# devboard.net
KiCad netlist of a schematic drawn in EAGLE
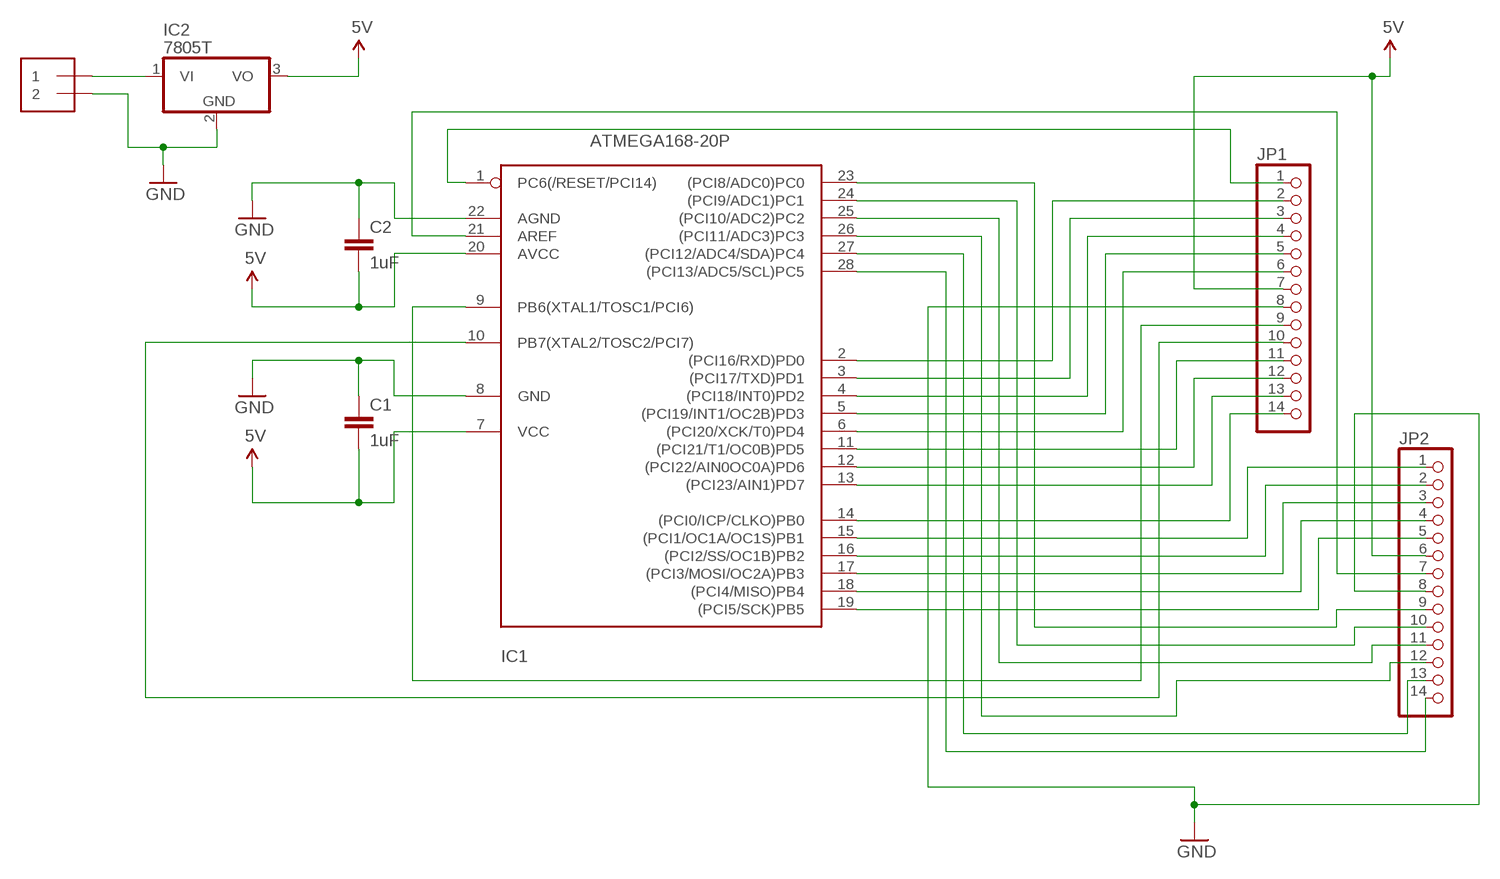
[diagram p0: schematic, sheet 1]

(export (version "E")
  (design (tool "Eeschema 10.0.6"))
  (components
    (comp (ref "C1")
      (value "1uF")
      (footprint "eagle-import:CAP-PTH-SMALL")
      (libsource (lib "eagle-import") (part "CAPPTH"))
    )
    (comp (ref "C2")
      (value "1uF")
      (footprint "eagle-import:CAP-PTH-SMALL")
      (libsource (lib "eagle-import") (part "CAPPTH"))
    )
    (comp (ref "IC1")
      (value "ATMEGA168-20P")
      (footprint "eagle-import:DIL28-3")
      (libsource (lib "eagle-import") (part "ATMEGA168P-20"))
    )
    (comp (ref "IC2")
      (value "7805T")
      (footprint "eagle-import:TO220H")
      (libsource (lib "eagle-import") (part "78T05"))
    )
    (comp (ref "JP1")
      (value "PINHD-1X14")
      (footprint "eagle-import:1X14")
      (libsource (lib "eagle-import") (part "PINHD-1X14"))
    )
    (comp (ref "JP2")
      (value "PINHD-1X14")
      (footprint "eagle-import:1X14")
      (libsource (lib "eagle-import") (part "PINHD-1X14"))
    )
    (comp (ref "POWER_IN")
      (value "1X2-3.5MM")
      (footprint "eagle-import:1X2-3.5MM")
      (libsource (lib "eagle-import") (part "1X2-3.5MM"))
    )
  )
  (nets
    (net (code "1") (name "5V") (class "Default")
      (node (ref "C1") (pin "2") (pinfunction "2_2") (pintype "passive"))
      (node (ref "C2") (pin "2") (pinfunction "2_2") (pintype "passive"))
      (node (ref "IC1") (pin "20") (pinfunction "AVCC_20") (pintype "bidirectional"))
      (node (ref "IC1") (pin "7") (pinfunction "VCC_7") (pintype "bidirectional"))
      (node (ref "IC2") (pin "3") (pinfunction "VO_3") (pintype "passive"))
      (node (ref "JP1") (pin "7") (pinfunction "7_7") (pintype "passive"))
      (node (ref "JP2") (pin "6") (pinfunction "6_6") (pintype "passive"))
    )
    (net (code "2") (name "GND") (class "Default")
      (node (ref "C1") (pin "1") (pinfunction "1_1") (pintype "passive"))
      (node (ref "C2") (pin "1") (pinfunction "1_1") (pintype "passive"))
      (node (ref "IC1") (pin "22") (pinfunction "AGND_22") (pintype "bidirectional"))
      (node (ref "IC1") (pin "8") (pinfunction "GND_8") (pintype "bidirectional"))
      (node (ref "IC2") (pin "2") (pinfunction "GND_2") (pintype "passive"))
      (node (ref "JP1") (pin "8") (pinfunction "8_8") (pintype "passive"))
      (node (ref "JP2") (pin "8") (pinfunction "8_8") (pintype "passive"))
      (node (ref "POWER_IN") (pin "2") (pinfunction "2_2") (pintype "passive"))
    )
    (net (code "3") (name "Net-(IC1-(PCI0{slash}ICP{slash}CLKO)PB0)") (class "Default")
      (node (ref "IC1") (pin "14") (pinfunction "(PCI0/ICP/CLKO)PB0_14") (pintype "bidirectional"))
      (node (ref "JP1") (pin "14") (pinfunction "14_14") (pintype "passive"))
    )
    (net (code "4") (name "Net-(IC1-(PCI1{slash}OC1A{slash}OC1S)PB1)") (class "Default")
      (node (ref "IC1") (pin "15") (pinfunction "(PCI1/OC1A/OC1S)PB1_15") (pintype "bidirectional"))
      (node (ref "JP2") (pin "1") (pinfunction "1_1") (pintype "passive"))
    )
    (net (code "5") (name "Net-(IC1-(PCI2{slash}SS{slash}OC1B)PB2)") (class "Default")
      (node (ref "IC1") (pin "16") (pinfunction "(PCI2/SS/OC1B)PB2_16") (pintype "bidirectional"))
      (node (ref "JP2") (pin "2") (pinfunction "2_2") (pintype "passive"))
    )
    (net (code "6") (name "Net-(IC1-(PCI3{slash}MOSI{slash}OC2A)PB3)") (class "Default")
      (node (ref "IC1") (pin "17") (pinfunction "(PCI3/MOSI/OC2A)PB3_17") (pintype "bidirectional"))
      (node (ref "JP2") (pin "3") (pinfunction "3_3") (pintype "passive"))
    )
    (net (code "7") (name "Net-(IC1-(PCI4{slash}MISO)PB4)") (class "Default")
      (node (ref "IC1") (pin "18") (pinfunction "(PCI4/MISO)PB4_18") (pintype "bidirectional"))
      (node (ref "JP2") (pin "4") (pinfunction "4_4") (pintype "passive"))
    )
    (net (code "8") (name "Net-(IC1-(PCI5{slash}SCK)PB5)") (class "Default")
      (node (ref "IC1") (pin "19") (pinfunction "(PCI5/SCK)PB5_19") (pintype "bidirectional"))
      (node (ref "JP2") (pin "5") (pinfunction "5_5") (pintype "passive"))
    )
    (net (code "9") (name "Net-(IC1-(PCI8{slash}ADC0)PC0)") (class "Default")
      (node (ref "IC1") (pin "23") (pinfunction "(PCI8/ADC0)PC0_23") (pintype "bidirectional"))
      (node (ref "JP2") (pin "9") (pinfunction "9_9") (pintype "passive"))
    )
    (net (code "10") (name "Net-(IC1-(PCI9{slash}ADC1)PC1)") (class "Default")
      (node (ref "IC1") (pin "24") (pinfunction "(PCI9/ADC1)PC1_24") (pintype "bidirectional"))
      (node (ref "JP2") (pin "10") (pinfunction "10_10") (pintype "passive"))
    )
    (net (code "11") (name "Net-(IC1-(PCI10{slash}ADC2)PC2)") (class "Default")
      (node (ref "IC1") (pin "25") (pinfunction "(PCI10/ADC2)PC2_25") (pintype "bidirectional"))
      (node (ref "JP2") (pin "11") (pinfunction "11_11") (pintype "passive"))
    )
    (net (code "12") (name "Net-(IC1-(PCI11{slash}ADC3)PC3)") (class "Default")
      (node (ref "IC1") (pin "26") (pinfunction "(PCI11/ADC3)PC3_26") (pintype "bidirectional"))
      (node (ref "JP2") (pin "12") (pinfunction "12_12") (pintype "passive"))
    )
    (net (code "13") (name "Net-(IC1-(PCI12{slash}ADC4{slash}SDA)PC4)") (class "Default")
      (node (ref "IC1") (pin "27") (pinfunction "(PCI12/ADC4/SDA)PC4_27") (pintype "bidirectional"))
      (node (ref "JP2") (pin "13") (pinfunction "13_13") (pintype "passive"))
    )
    (net (code "14") (name "Net-(IC1-(PCI13{slash}ADC5{slash}SCL)PC5)") (class "Default")
      (node (ref "IC1") (pin "28") (pinfunction "(PCI13/ADC5/SCL)PC5_28") (pintype "bidirectional"))
      (node (ref "JP2") (pin "14") (pinfunction "14_14") (pintype "passive"))
    )
    (net (code "15") (name "Net-(IC1-(PCI16{slash}RXD)PD0)") (class "Default")
      (node (ref "IC1") (pin "2") (pinfunction "(PCI16/RXD)PD0_2") (pintype "bidirectional"))
      (node (ref "JP1") (pin "2") (pinfunction "2_2") (pintype "passive"))
    )
    (net (code "16") (name "Net-(IC1-(PCI17{slash}TXD)PD1)") (class "Default")
      (node (ref "IC1") (pin "3") (pinfunction "(PCI17/TXD)PD1_3") (pintype "bidirectional"))
      (node (ref "JP1") (pin "3") (pinfunction "3_3") (pintype "passive"))
    )
    (net (code "17") (name "Net-(IC1-(PCI18{slash}INT0)PD2)") (class "Default")
      (node (ref "IC1") (pin "4") (pinfunction "(PCI18/INT0)PD2_4") (pintype "bidirectional"))
      (node (ref "JP1") (pin "4") (pinfunction "4_4") (pintype "passive"))
    )
    (net (code "18") (name "Net-(IC1-(PCI19{slash}INT1{slash}OC2B)PD3)") (class "Default")
      (node (ref "IC1") (pin "5") (pinfunction "(PCI19/INT1/OC2B)PD3_5") (pintype "bidirectional"))
      (node (ref "JP1") (pin "5") (pinfunction "5_5") (pintype "passive"))
    )
    (net (code "19") (name "Net-(IC1-(PCI20{slash}XCK{slash}T0)PD4)") (class "Default")
      (node (ref "IC1") (pin "6") (pinfunction "(PCI20/XCK/T0)PD4_6") (pintype "bidirectional"))
      (node (ref "JP1") (pin "6") (pinfunction "6_6") (pintype "passive"))
    )
    (net (code "20") (name "Net-(IC1-(PCI21{slash}T1{slash}OC0B)PD5)") (class "Default")
      (node (ref "IC1") (pin "11") (pinfunction "(PCI21/T1/OC0B)PD5_11") (pintype "bidirectional"))
      (node (ref "JP1") (pin "11") (pinfunction "11_11") (pintype "passive"))
    )
    (net (code "21") (name "Net-(IC1-(PCI22{slash}AIN0OC0A)PD6)") (class "Default")
      (node (ref "IC1") (pin "12") (pinfunction "(PCI22/AIN0OC0A)PD6_12") (pintype "bidirectional"))
      (node (ref "JP1") (pin "12") (pinfunction "12_12") (pintype "passive"))
    )
    (net (code "22") (name "Net-(IC1-(PCI23{slash}AIN1)PD7)") (class "Default")
      (node (ref "IC1") (pin "13") (pinfunction "(PCI23/AIN1)PD7_13") (pintype "bidirectional"))
      (node (ref "JP1") (pin "13") (pinfunction "13_13") (pintype "passive"))
    )
    (net (code "23") (name "Net-(IC1-AREF)") (class "Default")
      (node (ref "IC1") (pin "21") (pinfunction "AREF_21") (pintype "bidirectional"))
      (node (ref "JP2") (pin "7") (pinfunction "7_7") (pintype "passive"))
    )
    (net (code "24") (name "Net-(IC1-PB6(XTAL1{slash}TOSC1{slash}PCI6))") (class "Default")
      (node (ref "IC1") (pin "9") (pinfunction "PB6(XTAL1/TOSC1/PCI6)_9") (pintype "bidirectional"))
      (node (ref "JP1") (pin "9") (pinfunction "9_9") (pintype "passive"))
    )
    (net (code "25") (name "Net-(IC1-PB7(XTAL2{slash}TOSC2{slash}PCI7))") (class "Default")
      (node (ref "IC1") (pin "10") (pinfunction "PB7(XTAL2/TOSC2/PCI7)_10") (pintype "bidirectional"))
      (node (ref "JP1") (pin "10") (pinfunction "10_10") (pintype "passive"))
    )
    (net (code "26") (name "Net-(IC1-PC6({slash}RESET{slash}PCI14))") (class "Default")
      (node (ref "IC1") (pin "1") (pinfunction "PC6(/RESET/PCI14)_1") (pintype "bidirectional"))
      (node (ref "JP1") (pin "1") (pinfunction "1_1") (pintype "passive"))
    )
    (net (code "27") (name "Net-(IC2-VI)") (class "Default")
      (node (ref "IC2") (pin "1") (pinfunction "VI_1") (pintype "input"))
      (node (ref "POWER_IN") (pin "1") (pinfunction "1_1") (pintype "passive"))
    )
  )
)
